# -_-.net
KiCad netlist of a schematic drawn in Altium Designer
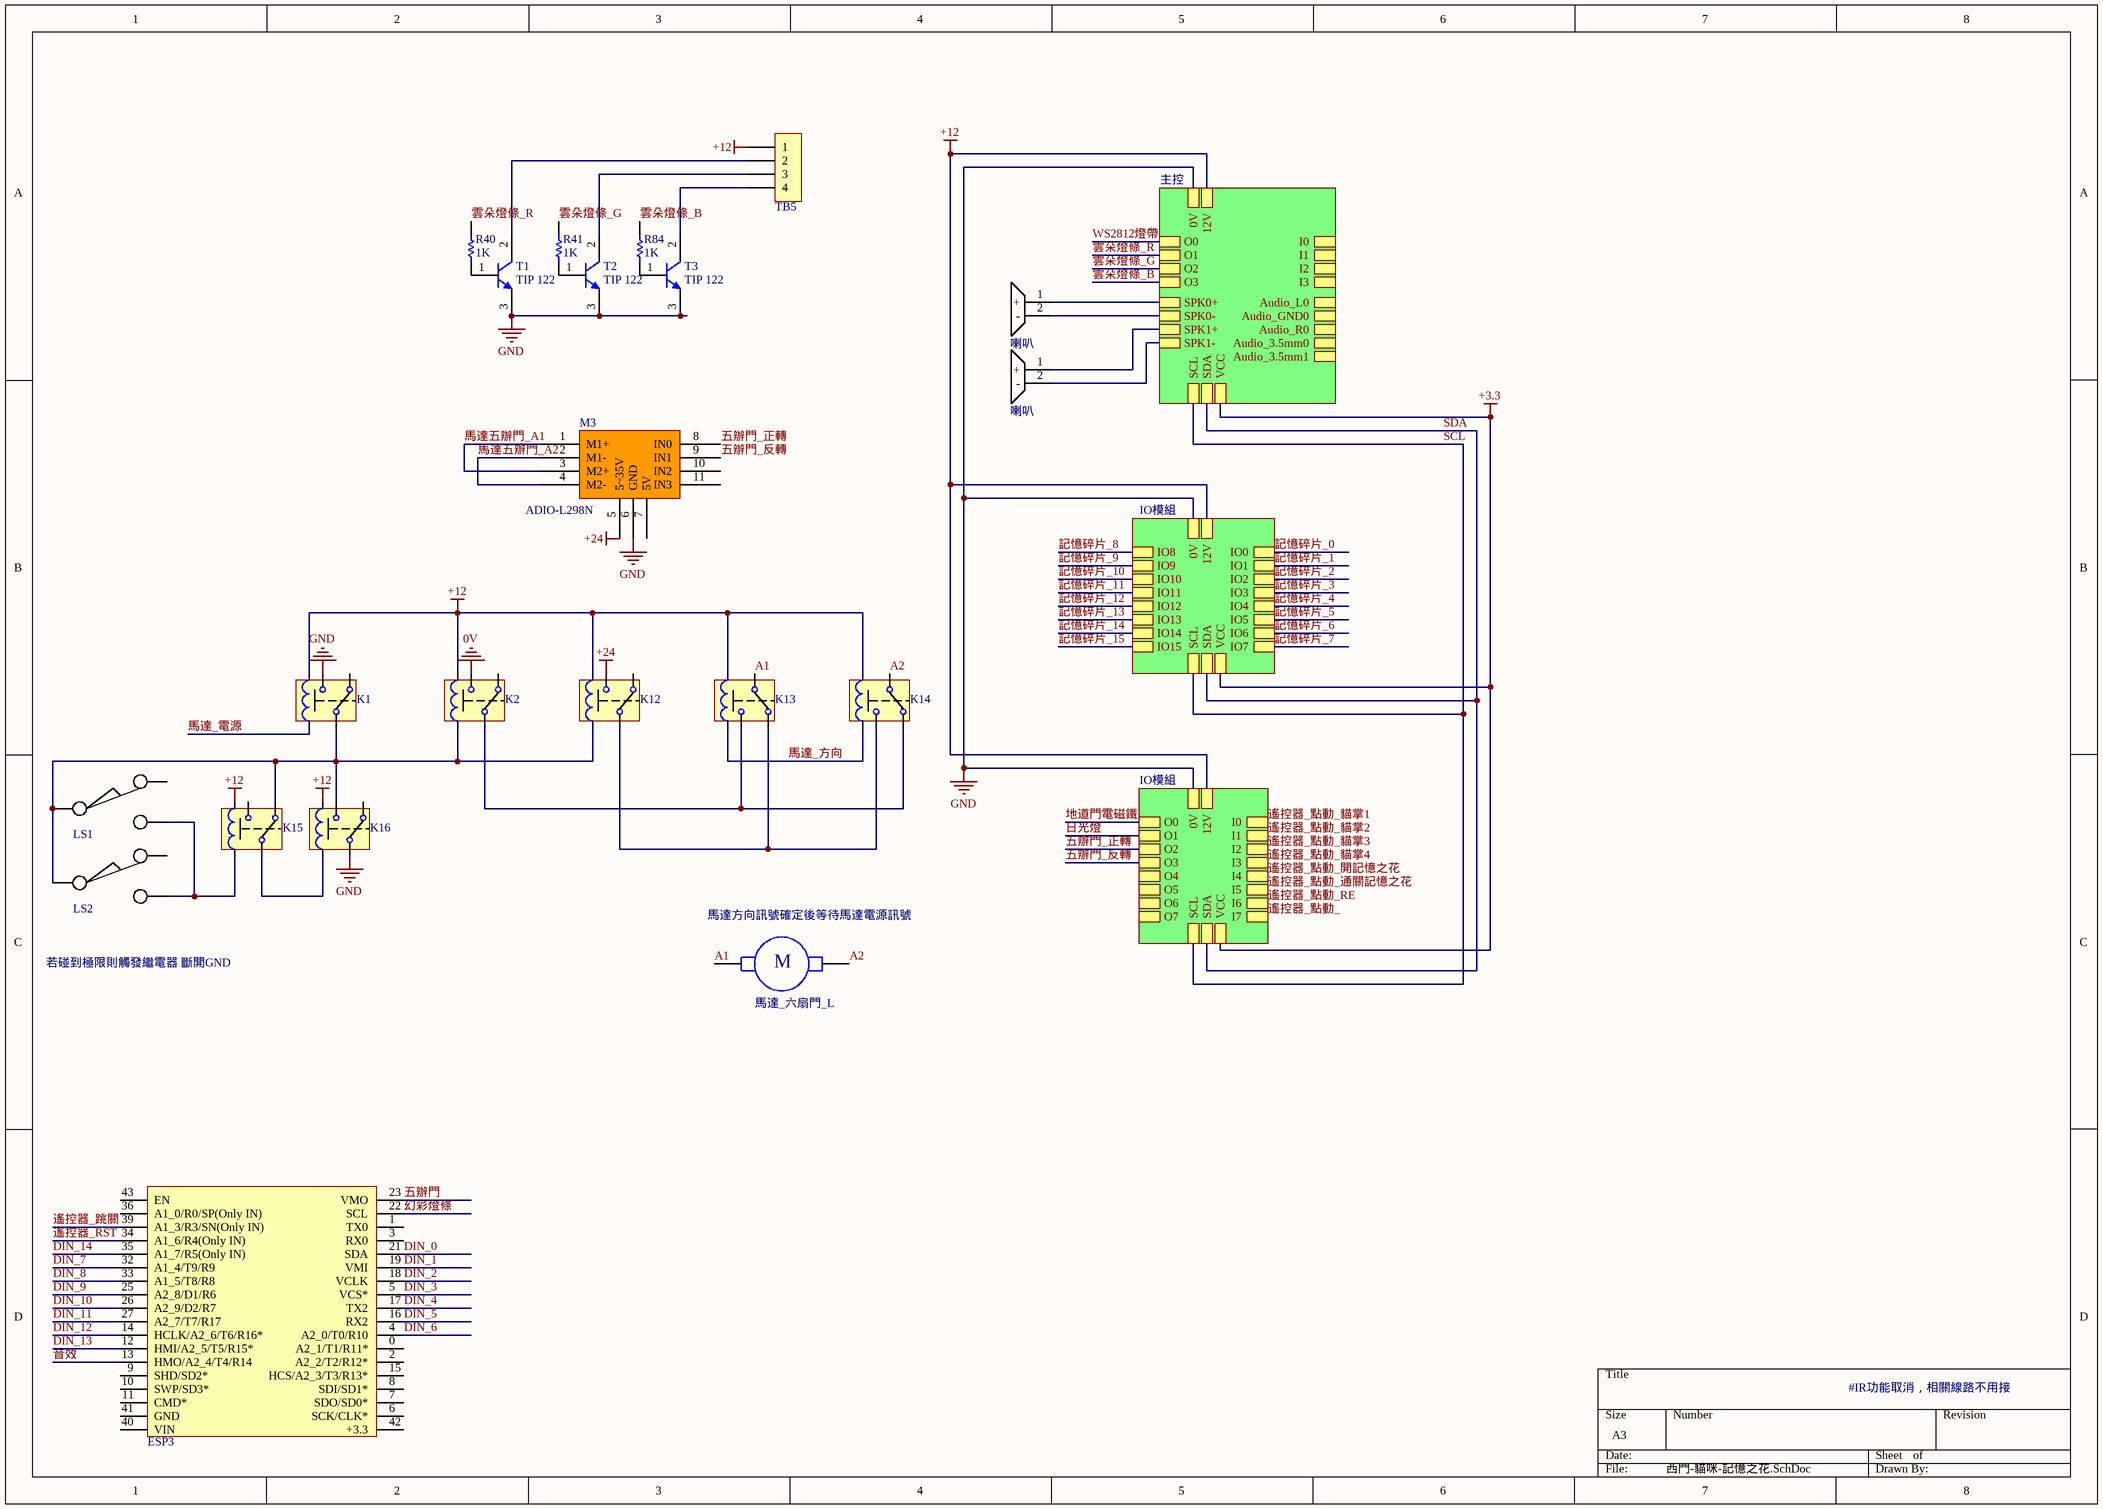
[diagram p0: 西門-貓咪-記憶之花.SchDoc]

(export (version "E")
  (design (tool "Eeschema 10.0.6"))
  (components
    (comp (ref "B16")
      (value "喇叭")
      (footprint "Buzzer_12085")
      (description "無源蜂鳴器")
      (libsource (lib "MyLibray") (part "Buzzer"))
    )
    (comp (ref "B17")
      (value "喇叭")
      (footprint "Buzzer_12085")
      (description "無源蜂鳴器")
      (libsource (lib "MyLibray") (part "Buzzer"))
    )
    (comp (ref "ESP3")
      (value "ESP32_Node32s")
      (footprint "ESP32 Module")
      (description "WIFI通訊模組")
      (libsource (lib "MyModule") (part "ESP32_Node32s"))
    )
    (comp (ref "K1")
      (value "G2R-1-24VDC")
      (footprint "RELAY-G2R-1")
      (description "繼電器")
      (libsource (lib "") (part "Relay_1"))
    )
    (comp (ref "K2")
      (value "G2R-1-24VDC")
      (footprint "RELAY-G2R-1")
      (description "繼電器")
      (libsource (lib "") (part "Relay_1"))
    )
    (comp (ref "K12")
      (value "G2R-1-24VDC")
      (footprint "RELAY-G2R-1")
      (description "繼電器")
      (libsource (lib "") (part "Relay_1"))
    )
    (comp (ref "K13")
      (value "G2R-1-24VDC")
      (footprint "RELAY-G2R-1")
      (description "繼電器")
      (libsource (lib "MyLibray") (part "Relay"))
    )
    (comp (ref "K14")
      (value "G2R-1-24VDC")
      (footprint "RELAY-G2R-1")
      (description "繼電器")
      (libsource (lib "MyLibray") (part "Relay"))
    )
    (comp (ref "K15")
      (value "G2R-1-24VDC")
      (footprint "RELAY-G2R-1")
      (description "繼電器")
      (libsource (lib "") (part "Relay_1"))
    )
    (comp (ref "K16")
      (value "G2R-1-24VDC")
      (footprint "RELAY-G2R-1")
      (description "繼電器")
      (libsource (lib "") (part "Relay_1"))
    )
    (comp (ref "LS1")
      (value "Limit switch")
      (description "極限開關")
      (libsource (lib "電機圖塊") (part "Limit switch"))
    )
    (comp (ref "LS2")
      (value "Limit switch")
      (description "極限開關")
      (libsource (lib "電機圖塊") (part "Limit switch"))
    )
    (comp (ref "M3")
      (value "ADIO-L298N")
      (footprint "L298N")
      (description "步進馬達控制、馬達正反轉模組")
      (libsource (lib "MyModule") (part "L298N"))
    )
    (comp (ref "MD6") (value "馬達_六扇門_L") (description "直流馬達") (libsource (lib "電機圖塊") (part "Motor_DC")))
    (comp (ref "R40")
      (value "1K")
      (footprint "Res-0201")
      (description "電阻")
      (libsource (lib "MyLibray") (part "Res"))
    )
    (comp (ref "R41")
      (value "1K")
      (footprint "Res-0201")
      (description "電阻")
      (libsource (lib "MyLibray") (part "Res"))
    )
    (comp (ref "R84")
      (value "1K")
      (footprint "Res-0201")
      (description "電阻")
      (libsource (lib "MyLibray") (part "Res"))
    )
    (comp (ref "T1")
      (value "TIP 122")
      (footprint "TO-220 1>2>3")
      (description "電晶體_NPN")
      (libsource (lib "MyLibray") (part "Transistor NPN"))
    )
    (comp (ref "T2")
      (value "TIP 122")
      (footprint "TO-220 1>2>3")
      (description "電晶體_NPN")
      (libsource (lib "MyLibray") (part "Transistor NPN"))
    )
    (comp (ref "T3")
      (value "TIP 122")
      (footprint "TO-220 1>2>3")
      (description "電晶體_NPN")
      (libsource (lib "MyLibray") (part "Transistor NPN"))
    )
    (comp (ref "TB5")
      (value "KF2EDGRT-5.08_4P")
      (footprint "Terminal block(KF2EDGR-3.81_4P)")
      (description "端子台")
      (libsource (lib "MyLibray") (part "Terminal block(4P)"))
    )
  )
  (nets
    (net (code "2") (name "+12") (class "Default")
      (node (ref "K1") (pin "5") (pinfunction "A2_5") (pintype "passive"))
      (node (ref "K12") (pin "5") (pinfunction "A2_5") (pintype "passive"))
      (node (ref "K13") (pin "4") (pinfunction "A1_4") (pintype "passive"))
      (node (ref "K14") (pin "4") (pinfunction "A1_4") (pintype "passive"))
      (node (ref "K15") (pin "5") (pinfunction "A2_5") (pintype "passive"))
      (node (ref "K16") (pin "5") (pinfunction "A2_5") (pintype "passive"))
      (node (ref "K2") (pin "5") (pinfunction "A2_5") (pintype "passive"))
      (node (ref "TB5") (pin "1") (pinfunction "1_1") (pintype "passive"))
    )
    (net (code "3") (name "+24") (class "Default")
      (node (ref "K12") (pin "2") (pinfunction "NO_2") (pintype "passive"))
      (node (ref "M3") (pin "5") (pinfunction "5~35V_5") (pintype "passive"))
    )
    (net (code "4") (name "/A1") (class "Default")
      (node (ref "K13") (pin "1") (pinfunction "COM_1") (pintype "passive"))
      (node (ref "MD6") (pin "4") (pinfunction "4_4") (pintype "power_in"))
    )
    (net (code "5") (name "/A2") (class "Default")
      (node (ref "K14") (pin "1") (pinfunction "COM_1") (pintype "passive"))
      (node (ref "MD6") (pin "4") (pinfunction "4_4") (pintype "power_in"))
    )
    (net (code "11") (name "/DIN_0") (class "Default")
      (node (ref "ESP3") (pin "21") (pinfunction "SDA_21") (pintype "passive"))
    )
    (net (code "12") (name "/DIN_1") (class "Default")
      (node (ref "ESP3") (pin "19") (pinfunction "VMI_19") (pintype "passive"))
    )
    (net (code "13") (name "/DIN_2") (class "Default")
      (node (ref "ESP3") (pin "18") (pinfunction "VCLK_18") (pintype "passive"))
    )
    (net (code "14") (name "/DIN_3") (class "Default")
      (node (ref "ESP3") (pin "5") (pinfunction "VCS*_5") (pintype "passive"))
    )
    (net (code "15") (name "/DIN_4") (class "Default")
      (node (ref "ESP3") (pin "17") (pinfunction "TX2_17") (pintype "passive"))
    )
    (net (code "16") (name "/DIN_5") (class "Default")
      (node (ref "ESP3") (pin "16") (pinfunction "RX2_16") (pintype "passive"))
    )
    (net (code "17") (name "/DIN_6") (class "Default")
      (node (ref "ESP3") (pin "4") (pinfunction "A2_0/T0/R10_4") (pintype "passive"))
    )
    (net (code "18") (name "/DIN_7") (class "Default")
      (node (ref "ESP3") (pin "32") (pinfunction "A1_4/T9/R9_32") (pintype "passive"))
    )
    (net (code "19") (name "/DIN_8") (class "Default")
      (node (ref "ESP3") (pin "33") (pinfunction "A1_5/T8/R8_33") (pintype "passive"))
    )
    (net (code "20") (name "/DIN_9") (class "Default")
      (node (ref "ESP3") (pin "25") (pinfunction "A2_8/D1/R6_25") (pintype "passive"))
    )
    (net (code "21") (name "/DIN_10") (class "Default")
      (node (ref "ESP3") (pin "26") (pinfunction "A2_9/D2/R7_26") (pintype "passive"))
    )
    (net (code "22") (name "/DIN_11") (class "Default")
      (node (ref "ESP3") (pin "27") (pinfunction "A2_7/T7/R17_27") (pintype "passive"))
    )
    (net (code "23") (name "/DIN_12") (class "Default")
      (node (ref "ESP3") (pin "14") (pinfunction "HCLK/A2_6/T6/R16*_14") (pintype "passive"))
    )
    (net (code "24") (name "/DIN_13") (class "Default")
      (node (ref "ESP3") (pin "12") (pinfunction "HMI/A2_5/T5/R15*_12") (pintype "passive"))
    )
    (net (code "25") (name "/DIN_14") (class "Default")
      (node (ref "ESP3") (pin "35") (pinfunction "A1_7/R5(Only_IN)_35") (pintype "passive"))
    )
    (net (code "36") (name "/SPK0+") (class "Default")
      (node (ref "B16") (pin "1") (pinfunction "+_1") (pintype "passive"))
    )
    (net (code "37") (name "/SPK0-") (class "Default")
      (node (ref "B16") (pin "2") (pinfunction "-_2") (pintype "passive"))
    )
    (net (code "38") (name "/SPK1+") (class "Default")
      (node (ref "B17") (pin "1") (pinfunction "+_1") (pintype "passive"))
    )
    (net (code "39") (name "/SPK1-") (class "Default")
      (node (ref "B17") (pin "2") (pinfunction "-_2") (pintype "passive"))
    )
    (net (code "41") (name "/五辦門") (class "Default")
      (node (ref "ESP3") (pin "23") (pinfunction "VMO_23") (pintype "passive"))
    )
    (net (code "42") (name "/五辦門_反轉") (class "Default")
      (node (ref "M3") (pin "9") (pinfunction "IN1_9") (pintype "passive"))
    )
    (net (code "43") (name "/五辦門_正轉") (class "Default")
      (node (ref "M3") (pin "8") (pinfunction "IN0_8") (pintype "passive"))
    )
    (net (code "45") (name "/幻彩燈條") (class "Default")
      (node (ref "ESP3") (pin "22") (pinfunction "SCL_22") (pintype "passive"))
    )
    (net (code "63") (name "/遙控器_RST") (class "Default")
      (node (ref "ESP3") (pin "34") (pinfunction "A1_6/R4(Only_IN)_34") (pintype "passive"))
    )
    (net (code "64") (name "/遙控器_跳關") (class "Default")
      (node (ref "ESP3") (pin "39") (pinfunction "A1_3/R3/SN(Only_IN)_39") (pintype "passive"))
    )
    (net (code "73") (name "/雲朵燈條_B") (class "Default")
      (node (ref "R84") (pin "1") (pinfunction "1_1") (pintype "passive"))
    )
    (net (code "74") (name "/雲朵燈條_G") (class "Default")
      (node (ref "R41") (pin "2") (pinfunction "2_2") (pintype "passive"))
    )
    (net (code "75") (name "/雲朵燈條_R") (class "Default")
      (node (ref "R40") (pin "2") (pinfunction "2_2") (pintype "passive"))
    )
    (net (code "76") (name "/音效") (class "Default")
      (node (ref "ESP3") (pin "13") (pinfunction "HMO/A2_4/T4/R14_13") (pintype "passive"))
    )
    (net (code "77") (name "/馬達_方向") (class "Default")
      (node (ref "K13") (pin "5") (pinfunction "A2_5") (pintype "passive"))
      (node (ref "K14") (pin "5") (pinfunction "A2_5") (pintype "passive"))
    )
    (net (code "78") (name "/馬達_電源") (class "Default")
      (node (ref "K1") (pin "4") (pinfunction "A1_4") (pintype "passive"))
    )
    (net (code "79") (name "/馬達五辦門_A1") (class "Default")
      (node (ref "M3") (pin "1") (pinfunction "M1+_1") (pintype "passive"))
      (node (ref "M3") (pin "3") (pinfunction "M2+_3") (pintype "passive"))
    )
    (net (code "80") (name "/馬達五辦門_A2") (class "Default")
      (node (ref "M3") (pin "2") (pinfunction "M1-_2") (pintype "passive"))
      (node (ref "M3") (pin "4") (pinfunction "M2-_4") (pintype "passive"))
    )
    (net (code "81") (name "0V") (class "Default")
      (node (ref "K2") (pin "2") (pinfunction "NO_2") (pintype "passive"))
    )
    (net (code "82") (name "GND") (class "Default")
      (node (ref "K1") (pin "2") (pinfunction "NO_2") (pintype "passive"))
      (node (ref "K16") (pin "1") (pinfunction "COM_1") (pintype "passive"))
      (node (ref "M3") (pin "6") (pinfunction "GND_6") (pintype "passive"))
      (node (ref "T1") (pin "3") (pinfunction "E_3") (pintype "passive"))
      (node (ref "T2") (pin "3") (pinfunction "E_3") (pintype "passive"))
      (node (ref "T3") (pin "3") (pinfunction "E_3") (pintype "passive"))
    )
    (net (code "83") (name "Net-(K1-COM)") (class "Default")
      (node (ref "K1") (pin "1") (pinfunction "COM_1") (pintype "passive"))
      (node (ref "K12") (pin "4") (pinfunction "A1_4") (pintype "passive"))
      (node (ref "K15") (pin "3") (pinfunction "NC_3") (pintype "passive"))
      (node (ref "K16") (pin "2") (pinfunction "NO_2") (pintype "passive"))
      (node (ref "K2") (pin "4") (pinfunction "A1_4") (pintype "passive"))
      (node (ref "LS1") (pin "1") (pinfunction "1_1") (pintype "passive"))
      (node (ref "LS2") (pin "1") (pinfunction "1_1") (pintype "passive"))
    )
    (net (code "84") (name "Net-(K12-COM)") (class "Default")
      (node (ref "K12") (pin "1") (pinfunction "COM_1") (pintype "passive"))
      (node (ref "K13") (pin "3") (pinfunction "NC_3") (pintype "passive"))
      (node (ref "K14") (pin "2") (pinfunction "NO_2") (pintype "passive"))
    )
    (net (code "85") (name "Net-(K13-NO)") (class "Default")
      (node (ref "K13") (pin "2") (pinfunction "NO_2") (pintype "passive"))
      (node (ref "K14") (pin "3") (pinfunction "NC_3") (pintype "passive"))
      (node (ref "K2") (pin "1") (pinfunction "COM_1") (pintype "passive"))
    )
    (net (code "86") (name "Net-(K15-A1)") (class "Default")
      (node (ref "K15") (pin "4") (pinfunction "A1_4") (pintype "passive"))
      (node (ref "LS1") (pin "2") (pinfunction "2_2") (pintype "passive"))
      (node (ref "LS2") (pin "2") (pinfunction "2_2") (pintype "passive"))
    )
    (net (code "87") (name "Net-(K15-COM)") (class "Default")
      (node (ref "K15") (pin "1") (pinfunction "COM_1") (pintype "passive"))
      (node (ref "K16") (pin "4") (pinfunction "A1_4") (pintype "passive"))
    )
    (net (code "88") (name "Net-(T1-B)") (class "Default")
      (node (ref "R40") (pin "1") (pinfunction "1_1") (pintype "passive"))
      (node (ref "T1") (pin "1") (pinfunction "B_1") (pintype "passive"))
    )
    (net (code "89") (name "Net-(T1-C)") (class "Default")
      (node (ref "T1") (pin "2") (pinfunction "C_2") (pintype "passive"))
      (node (ref "TB5") (pin "2") (pinfunction "2_2") (pintype "passive"))
    )
    (net (code "90") (name "Net-(T2-B)") (class "Default")
      (node (ref "R41") (pin "1") (pinfunction "1_1") (pintype "passive"))
      (node (ref "T2") (pin "1") (pinfunction "B_1") (pintype "passive"))
    )
    (net (code "91") (name "Net-(T2-C)") (class "Default")
      (node (ref "T2") (pin "2") (pinfunction "C_2") (pintype "passive"))
      (node (ref "TB5") (pin "3") (pinfunction "3_3") (pintype "passive"))
    )
    (net (code "92") (name "Net-(T3-B)") (class "Default")
      (node (ref "R84") (pin "2") (pinfunction "2_2") (pintype "passive"))
      (node (ref "T3") (pin "1") (pinfunction "B_1") (pintype "passive"))
    )
    (net (code "93") (name "Net-(T3-C)") (class "Default")
      (node (ref "T3") (pin "2") (pinfunction "C_2") (pintype "passive"))
      (node (ref "TB5") (pin "4") (pinfunction "4_4") (pintype "passive"))
    )
    (net (code "94") (name "unconnected-(ESP3-+3.3-Pad42)") (class "Default")
      (node (ref "ESP3") (pin "42") (pinfunction "+3.3_42") (pintype "passive"))
    )
    (net (code "95") (name "unconnected-(ESP3-A1_0{slash}R0{slash}SP(Only_IN)-Pad36)") (class "Default")
      (node (ref "ESP3") (pin "36") (pinfunction "A1_0/R0/SP(Only_IN)_36") (pintype "passive"))
    )
    (net (code "96") (name "unconnected-(ESP3-A2_1{slash}T1{slash}R11*-Pad0)") (class "Default")
      (node (ref "ESP3") (pin "0") (pinfunction "A2_1/T1/R11*_0") (pintype "passive"))
    )
    (net (code "97") (name "unconnected-(ESP3-A2_2{slash}T2{slash}R12*-Pad2)") (class "Default")
      (node (ref "ESP3") (pin "2") (pinfunction "A2_2/T2/R12*_2") (pintype "passive"))
    )
    (net (code "98") (name "unconnected-(ESP3-CMD*-Pad11)") (class "Default")
      (node (ref "ESP3") (pin "11") (pinfunction "CMD*_11") (pintype "passive"))
    )
    (net (code "99") (name "unconnected-(ESP3-EN-Pad43)") (class "Default")
      (node (ref "ESP3") (pin "43") (pinfunction "EN_43") (pintype "passive"))
    )
    (net (code "100") (name "unconnected-(ESP3-GND-Pad41)") (class "Default")
      (node (ref "ESP3") (pin "41") (pinfunction "GND_41") (pintype "power_in"))
    )
    (net (code "101") (name "unconnected-(ESP3-HCS{slash}A2_3{slash}T3{slash}R13*-Pad15)") (class "Default")
      (node (ref "ESP3") (pin "15") (pinfunction "HCS/A2_3/T3/R13*_15") (pintype "passive"))
    )
    (net (code "102") (name "unconnected-(ESP3-RX0-Pad3)") (class "Default")
      (node (ref "ESP3") (pin "3") (pinfunction "RX0_3") (pintype "passive"))
    )
    (net (code "103") (name "unconnected-(ESP3-SCK{slash}CLK*-Pad6)") (class "Default")
      (node (ref "ESP3") (pin "6") (pinfunction "SCK/CLK*_6") (pintype "passive"))
    )
    (net (code "104") (name "unconnected-(ESP3-SDI{slash}SD1*-Pad8)") (class "Default")
      (node (ref "ESP3") (pin "8") (pinfunction "SDI/SD1*_8") (pintype "passive"))
    )
    (net (code "105") (name "unconnected-(ESP3-SDO{slash}SD0*-Pad7)") (class "Default")
      (node (ref "ESP3") (pin "7") (pinfunction "SDO/SD0*_7") (pintype "passive"))
    )
    (net (code "106") (name "unconnected-(ESP3-SHD{slash}SD2*-Pad9)") (class "Default")
      (node (ref "ESP3") (pin "9") (pinfunction "SHD/SD2*_9") (pintype "passive"))
    )
    (net (code "107") (name "unconnected-(ESP3-SWP{slash}SD3*-Pad10)") (class "Default")
      (node (ref "ESP3") (pin "10") (pinfunction "SWP/SD3*_10") (pintype "passive"))
    )
    (net (code "108") (name "unconnected-(ESP3-TX0-Pad1)") (class "Default")
      (node (ref "ESP3") (pin "1") (pinfunction "TX0_1") (pintype "passive"))
    )
    (net (code "109") (name "unconnected-(ESP3-VIN-Pad40)") (class "Default")
      (node (ref "ESP3") (pin "40") (pinfunction "VIN_40") (pintype "passive"))
    )
    (net (code "110") (name "unconnected-(K1-NC-Pad3)") (class "Default")
      (node (ref "K1") (pin "3") (pinfunction "NC_3") (pintype "passive"))
    )
    (net (code "111") (name "unconnected-(K2-NC-Pad3)") (class "Default")
      (node (ref "K2") (pin "3") (pinfunction "NC_3") (pintype "passive"))
    )
    (net (code "112") (name "unconnected-(K12-NC-Pad3)") (class "Default")
      (node (ref "K12") (pin "3") (pinfunction "NC_3") (pintype "passive"))
    )
    (net (code "113") (name "unconnected-(K15-NO-Pad2)") (class "Default")
      (node (ref "K15") (pin "2") (pinfunction "NO_2") (pintype "passive"))
    )
    (net (code "114") (name "unconnected-(K16-NC-Pad3)") (class "Default")
      (node (ref "K16") (pin "3") (pinfunction "NC_3") (pintype "passive"))
    )
    (net (code "115") (name "unconnected-(LS1-Pad3)") (class "Default")
      (node (ref "LS1") (pin "3") (pinfunction "3_3") (pintype "passive"))
    )
    (net (code "116") (name "unconnected-(LS2-Pad3)") (class "Default")
      (node (ref "LS2") (pin "3") (pinfunction "3_3") (pintype "passive"))
    )
    (net (code "117") (name "unconnected-(M3-5V-Pad7)") (class "Default")
      (node (ref "M3") (pin "7") (pinfunction "5V_7") (pintype "passive"))
    )
    (net (code "118") (name "unconnected-(M3-IN2-Pad10)") (class "Default")
      (node (ref "M3") (pin "10") (pinfunction "IN2_10") (pintype "passive"))
    )
    (net (code "119") (name "unconnected-(M3-IN3-Pad11)") (class "Default")
      (node (ref "M3") (pin "11") (pinfunction "IN3_11") (pintype "passive"))
    )
  )
)
